# comperator_3dprinterV2.net
KiCad netlist of a schematic drawn in EAGLE
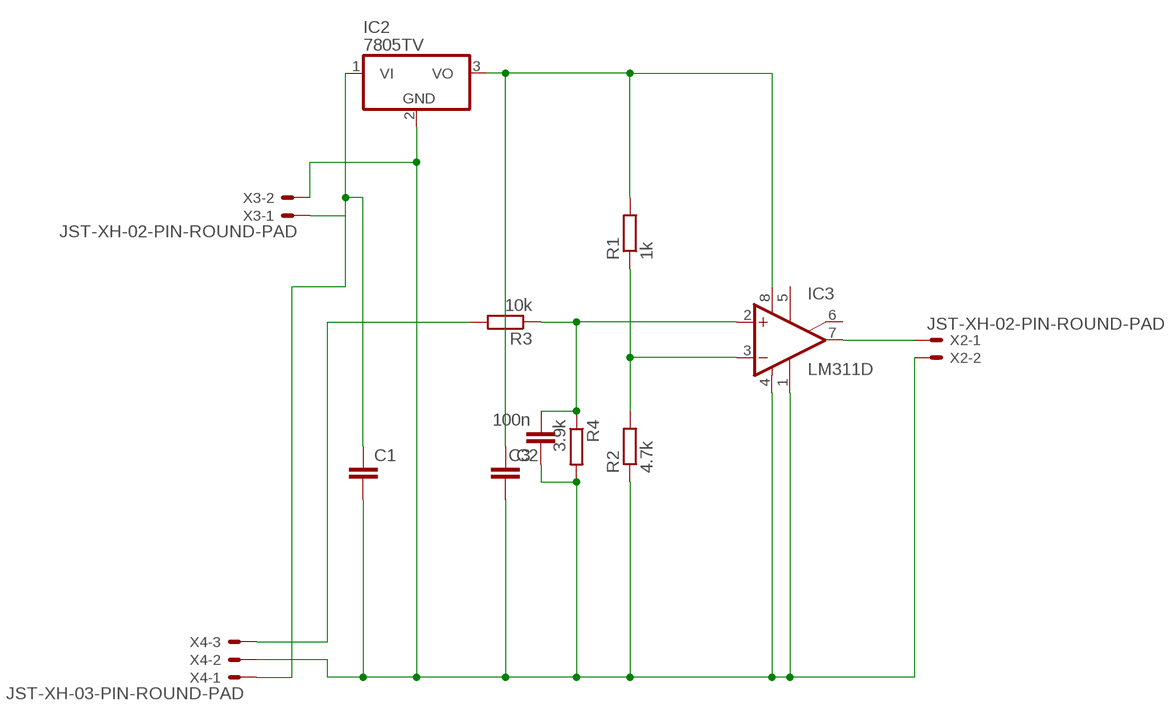
[diagram p0: schematic, sheet 1]

(export (version "E")
  (design (tool "Eeschema 10.0.6"))
  (components
    (comp (ref "C1")
      (value "C2.5/2")
      (footprint "eagle-import:C2.5-2")
      (libsource (lib "eagle-import") (part "C2.5/2"))
    )
    (comp (ref "C2")
      (value "C2.5/2")
      (footprint "eagle-import:C2.5-2")
      (libsource (lib "eagle-import") (part "C2.5/2"))
    )
    (comp (ref "C3")
      (value "100n")
      (footprint "eagle-import:C2.5-2")
      (libsource (lib "eagle-import") (part "C2.5/2"))
    )
    (comp (ref "IC2")
      (value "7805TV")
      (footprint "eagle-import:TO220V")
      (libsource (lib "eagle-import") (part "78TV05"))
    )
    (comp (ref "IC3")
      (value "LM311D")
      (footprint "eagle-import:SO08")
      (libsource (lib "eagle-import") (part "LM311D"))
    )
    (comp (ref "R1")
      (value "1k")
      (footprint "eagle-import:0207_7")
      (libsource (lib "eagle-import") (part "R-EU_0207/7"))
    )
    (comp (ref "R2")
      (value "4.7k")
      (footprint "eagle-import:0207_7")
      (libsource (lib "eagle-import") (part "R-EU_0207/7"))
    )
    (comp (ref "R3")
      (value "10k")
      (footprint "eagle-import:0207_7")
      (libsource (lib "eagle-import") (part "R-EU_0207/7"))
    )
    (comp (ref "R4")
      (value "3.9k")
      (footprint "eagle-import:0207_7")
      (libsource (lib "eagle-import") (part "R-EU_0207/7"))
    )
    (comp (ref "X2")
      (value "JST-XH-02-PIN-ROUND-PAD")
      (footprint "eagle-import:JST-XH-02-PACKAGE-ROUND-PAD")
      (libsource (lib "eagle-import") (part "JST-XH-02-PIN-ROUND-PAD"))
    )
    (comp (ref "X3")
      (value "JST-XH-02-PIN-ROUND-PAD")
      (footprint "eagle-import:JST-XH-02-PACKAGE-ROUND-PAD")
      (libsource (lib "eagle-import") (part "JST-XH-02-PIN-ROUND-PAD"))
    )
    (comp (ref "X4")
      (value "JST-XH-03-PIN-ROUND-PAD")
      (footprint "eagle-import:JST-XH-03-PACKAGE-ROUND-PAD")
      (libsource (lib "eagle-import") (part "JST-XH-03-PIN-ROUND-PAD"))
    )
  )
  (nets
    (net (code "1") (name "Net-(IC2-GND)") (class "Default")
      (node (ref "C1") (pin "2") (pinfunction "2_2") (pintype "passive"))
      (node (ref "C2") (pin "2") (pinfunction "2_2") (pintype "passive"))
      (node (ref "C3") (pin "1") (pinfunction "1_1") (pintype "passive"))
      (node (ref "IC2") (pin "2") (pinfunction "GND_2") (pintype "passive"))
      (node (ref "IC3") (pin "1") (pinfunction "GND_1") (pintype "passive"))
      (node (ref "IC3") (pin "4") (pinfunction "V-_4") (pintype "power_in"))
      (node (ref "R2") (pin "1") (pinfunction "1_1") (pintype "passive"))
      (node (ref "R4") (pin "2") (pinfunction "2_2") (pintype "passive"))
      (node (ref "X2") (pin "2") (pinfunction "S_2") (pintype "passive"))
      (node (ref "X3") (pin "2") (pinfunction "S_2") (pintype "passive"))
      (node (ref "X4") (pin "2") (pinfunction "S_2") (pintype "passive"))
    )
    (net (code "2") (name "Net-(IC2-VI)") (class "Default")
      (node (ref "C1") (pin "1") (pinfunction "1_1") (pintype "passive"))
      (node (ref "IC2") (pin "1") (pinfunction "VI_1") (pintype "input"))
      (node (ref "X3") (pin "1") (pinfunction "S_1") (pintype "passive"))
      (node (ref "X4") (pin "1") (pinfunction "S_1") (pintype "passive"))
    )
    (net (code "3") (name "Net-(IC2-VO)") (class "Default")
      (node (ref "C2") (pin "1") (pinfunction "1_1") (pintype "passive"))
      (node (ref "IC2") (pin "3") (pinfunction "VO_3") (pintype "passive"))
      (node (ref "IC3") (pin "8") (pinfunction "V+_8") (pintype "power_in"))
      (node (ref "R1") (pin "2") (pinfunction "2_2") (pintype "passive"))
    )
    (net (code "4") (name "Net-(IC3-+IN)") (class "Default")
      (node (ref "C3") (pin "2") (pinfunction "2_2") (pintype "passive"))
      (node (ref "IC3") (pin "2") (pinfunction "+IN_2") (pintype "input"))
      (node (ref "R3") (pin "1") (pinfunction "1_1") (pintype "passive"))
      (node (ref "R4") (pin "1") (pinfunction "1_1") (pintype "passive"))
    )
    (net (code "5") (name "Net-(IC3--IN)") (class "Default")
      (node (ref "IC3") (pin "3") (pinfunction "-IN_3") (pintype "input"))
      (node (ref "R1") (pin "1") (pinfunction "1_1") (pintype "passive"))
      (node (ref "R2") (pin "2") (pinfunction "2_2") (pintype "passive"))
    )
    (net (code "6") (name "Net-(IC3-OUT)") (class "Default")
      (node (ref "IC3") (pin "7") (pinfunction "OUT_7") (pintype "output"))
      (node (ref "X2") (pin "1") (pinfunction "S_1") (pintype "passive"))
    )
    (net (code "7") (name "Net-(X4C-S)") (class "Default")
      (node (ref "R3") (pin "2") (pinfunction "2_2") (pintype "passive"))
      (node (ref "X4") (pin "3") (pinfunction "S_3") (pintype "passive"))
    )
    (net (code "8") (name "unconnected-(IC3-ON-Pad5)") (class "Default")
      (node (ref "IC3") (pin "5") (pinfunction "ON_5") (pintype "passive"))
    )
    (net (code "9") (name "unconnected-(IC3-ON{slash}STR-Pad6)") (class "Default")
      (node (ref "IC3") (pin "6") (pinfunction "ON/STR_6") (pintype "passive"))
    )
  )
)
